# Celestron_Telescope_GPSRX-BT-WiFi-1_10.net
KiCad netlist of a schematic drawn in EAGLE
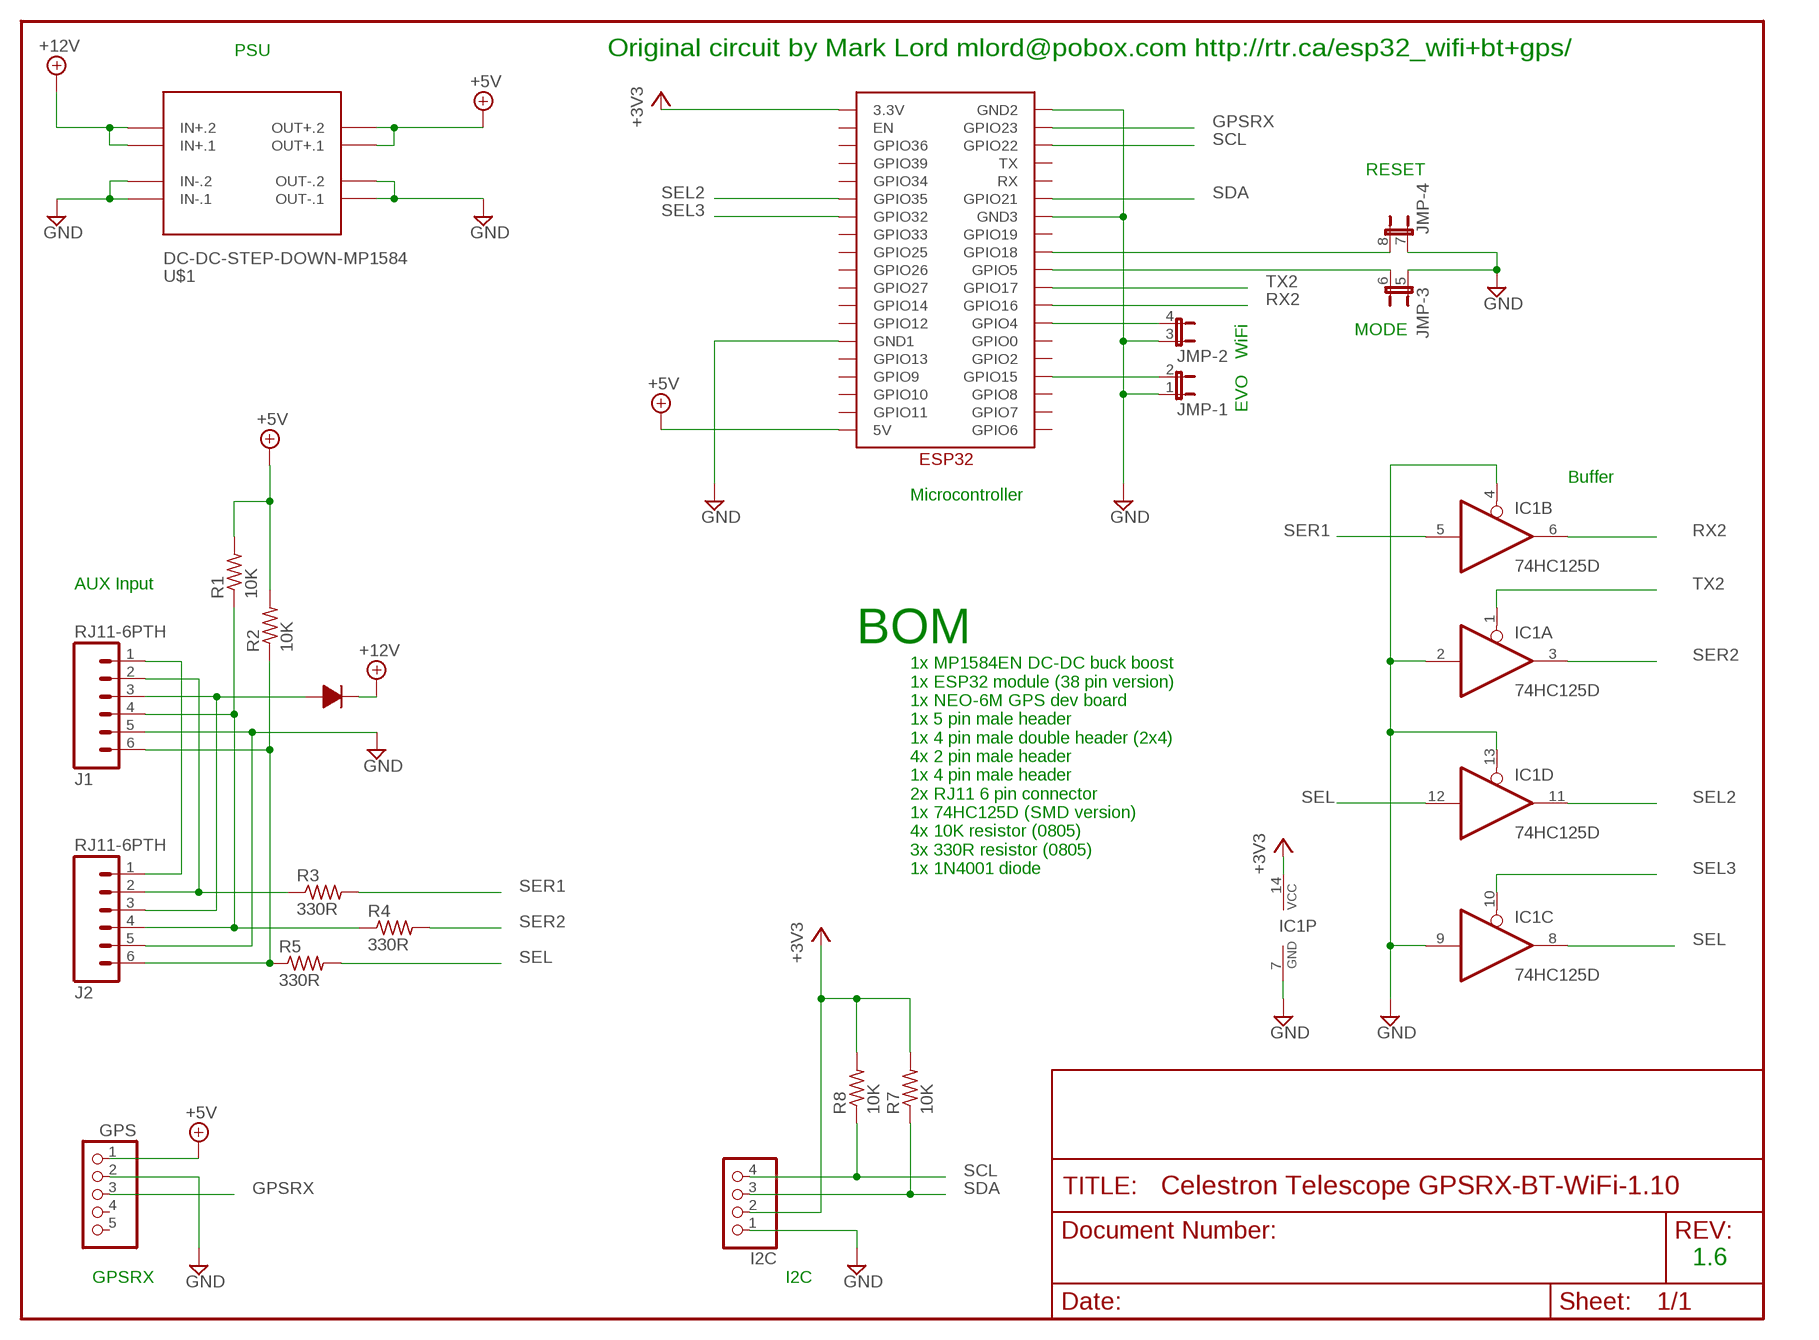
[diagram p0: schematic, sheet 1]

(export (version "E")
  (design (tool "Eeschema 10.0.6"))
  (components
    (comp (ref "GPS")
      (value "PINHD-1X5")
      (footprint "eagle-import:1X05")
      (libsource (lib "eagle-import") (part "PINHD-1X5"))
    )
    (comp (ref "I2C")
      (value "PINHD-1X4")
      (footprint "eagle-import:1X04")
      (libsource (lib "eagle-import") (part "PINHD-1X4"))
    )
    (comp (ref "IC1")
      (value "74HC125D")
      (footprint "eagle-import:SO14")
      (libsource (lib "eagle-import") (part "74125DHC"))
    )
    (comp (ref "J1")
      (value "RJ11-6PTH")
      (footprint "eagle-import:RJ11-6")
      (libsource (lib "eagle-import") (part "RJ11-6PTH"))
    )
    (comp (ref "J2")
      (value "RJ11-6PTH")
      (footprint "eagle-import:RJ11-6")
      (libsource (lib "eagle-import") (part "RJ11-6PTH"))
    )
    (comp (ref "JMP")
      (value "JP4QE")
      (footprint "eagle-import:JP4Q")
      (libsource (lib "eagle-import") (part "JP4QE"))
    )
    (comp (ref "R1")
      (value "10K")
      (footprint "eagle-import:M0805")
      (libsource (lib "eagle-import") (part "R-US_M0805"))
    )
    (comp (ref "R2")
      (value "10K")
      (footprint "eagle-import:M0805")
      (libsource (lib "eagle-import") (part "R-US_M0805"))
    )
    (comp (ref "R3")
      (value "330R")
      (footprint "eagle-import:M0805")
      (libsource (lib "eagle-import") (part "R-US_M0805"))
    )
    (comp (ref "R4")
      (value "330R")
      (footprint "eagle-import:M0805")
      (libsource (lib "eagle-import") (part "R-US_M0805"))
    )
    (comp (ref "R5")
      (value "330R")
      (footprint "eagle-import:M0805")
      (libsource (lib "eagle-import") (part "R-US_M0805"))
    )
    (comp (ref "R7")
      (value "10K")
      (footprint "eagle-import:M0805")
      (libsource (lib "eagle-import") (part "R-US_M0805"))
    )
    (comp (ref "R8")
      (value "10K")
      (footprint "eagle-import:M0805")
      (libsource (lib "eagle-import") (part "R-US_M0805"))
    )
    (comp (ref "U$1")
      (value "DC-DC-STEP-DOWN-MP1584")
      (footprint "eagle-import:DC-DC-STEP-DOWN-MP1584")
      (libsource (lib "eagle-import") (part "DC-DC-STEP-DOWN-MP1584"))
    )
    (comp (ref "U$2")
      (value "1N4001")
      (footprint "eagle-import:DIODE-12.70")
      (libsource (lib "eagle-import") (part "1N4001"))
    )
    (comp (ref "U$3")
      (value "ESP32")
      (footprint "eagle-import:ESP32")
      (libsource (lib "eagle-import") (part "ESP32"))
    )
  )
  (nets
    (net (code "1") (name "+3V3") (class "Default")
      (node (ref "I2C") (pin "2") (pinfunction "2_2") (pintype "passive"))
      (node (ref "IC1") (pin "14") (pinfunction "VCC_14") (pintype "power_in"))
      (node (ref "R7") (pin "2") (pinfunction "2_2") (pintype "passive"))
      (node (ref "R8") (pin "2") (pinfunction "2_2") (pintype "passive"))
      (node (ref "U$3") (pin "3.3V") (pinfunction "3.3V_3.3V") (pintype "bidirectional"))
    )
    (net (code "2") (name "+5V") (class "Default")
      (node (ref "GPS") (pin "1") (pinfunction "1_1") (pintype "passive"))
      (node (ref "R1") (pin "2") (pinfunction "2_2") (pintype "passive"))
      (node (ref "R2") (pin "2") (pinfunction "2_2") (pintype "passive"))
      (node (ref "U$1") (pin "OUT+.1") (pinfunction "OUT+.1_OUT+.1") (pintype "bidirectional"))
      (node (ref "U$1") (pin "OUT+.2") (pinfunction "OUT+.2_OUT+.2") (pintype "bidirectional"))
      (node (ref "U$3") (pin "5V") (pinfunction "5V_5V") (pintype "bidirectional"))
    )
    (net (code "3") (name "+12V") (class "Default")
      (node (ref "U$1") (pin "IN+.1") (pinfunction "IN+.1_IN+.1") (pintype "bidirectional"))
      (node (ref "U$1") (pin "IN+.2") (pinfunction "IN+.2_IN+.2") (pintype "bidirectional"))
      (node (ref "U$2") (pin "P$2") (pinfunction "P$2_P$2") (pintype "passive"))
    )
    (net (code "4") (name "/GPSRX") (class "Default")
      (node (ref "GPS") (pin "3") (pinfunction "3_3") (pintype "passive"))
      (node (ref "U$3") (pin "GPIO23") (pinfunction "GPIO23_GPIO23") (pintype "bidirectional"))
    )
    (net (code "5") (name "/RX2") (class "Default")
      (node (ref "IC1") (pin "6") (pinfunction "O_6") (pintype "tri_state"))
      (node (ref "U$3") (pin "GPIO16") (pinfunction "GPIO16_GPIO16") (pintype "bidirectional"))
    )
    (net (code "6") (name "/SCL") (class "Default")
      (node (ref "I2C") (pin "4") (pinfunction "4_4") (pintype "passive"))
      (node (ref "R8") (pin "1") (pinfunction "1_1") (pintype "passive"))
      (node (ref "U$3") (pin "GPIO22") (pinfunction "GPIO22_GPIO22") (pintype "bidirectional"))
    )
    (net (code "7") (name "/SDA") (class "Default")
      (node (ref "I2C") (pin "3") (pinfunction "3_3") (pintype "passive"))
      (node (ref "R7") (pin "1") (pinfunction "1_1") (pintype "passive"))
      (node (ref "U$3") (pin "GPIO21") (pinfunction "GPIO21_GPIO21") (pintype "bidirectional"))
    )
    (net (code "8") (name "/SEL") (class "Default")
      (node (ref "IC1") (pin "12") (pinfunction "I_12") (pintype "input"))
      (node (ref "IC1") (pin "8") (pinfunction "O_8") (pintype "tri_state"))
      (node (ref "R5") (pin "2") (pinfunction "2_2") (pintype "passive"))
    )
    (net (code "9") (name "/SEL2") (class "Default")
      (node (ref "IC1") (pin "11") (pinfunction "O_11") (pintype "tri_state"))
      (node (ref "U$3") (pin "GPIO35") (pinfunction "GPIO35_GPIO35") (pintype "bidirectional"))
    )
    (net (code "10") (name "/SEL3") (class "Default")
      (node (ref "IC1") (pin "10") (pinfunction "OE_10") (pintype "input"))
      (node (ref "U$3") (pin "GPIO32") (pinfunction "GPIO32_GPIO32") (pintype "bidirectional"))
    )
    (net (code "11") (name "/SER1") (class "Default")
      (node (ref "IC1") (pin "5") (pinfunction "I_5") (pintype "input"))
      (node (ref "R3") (pin "2") (pinfunction "2_2") (pintype "passive"))
    )
    (net (code "12") (name "/SER2") (class "Default")
      (node (ref "IC1") (pin "3") (pinfunction "O_3") (pintype "tri_state"))
      (node (ref "R4") (pin "2") (pinfunction "2_2") (pintype "passive"))
    )
    (net (code "13") (name "/TX2") (class "Default")
      (node (ref "IC1") (pin "1") (pinfunction "OE_1") (pintype "input"))
      (node (ref "U$3") (pin "GPIO17") (pinfunction "GPIO17_GPIO17") (pintype "bidirectional"))
    )
    (net (code "14") (name "GND") (class "Default")
      (node (ref "GPS") (pin "2") (pinfunction "2_2") (pintype "passive"))
      (node (ref "I2C") (pin "1") (pinfunction "1_1") (pintype "passive"))
      (node (ref "IC1") (pin "13") (pinfunction "OE_13") (pintype "input"))
      (node (ref "IC1") (pin "2") (pinfunction "I_2") (pintype "input"))
      (node (ref "IC1") (pin "4") (pinfunction "OE_4") (pintype "input"))
      (node (ref "IC1") (pin "7") (pinfunction "GND_7") (pintype "power_in"))
      (node (ref "IC1") (pin "9") (pinfunction "I_9") (pintype "input"))
      (node (ref "J1") (pin "5") (pinfunction "5_5") (pintype "passive"))
      (node (ref "J2") (pin "5") (pinfunction "5_5") (pintype "passive"))
      (node (ref "JMP") (pin "1") (pinfunction "1_1") (pintype "passive"))
      (node (ref "JMP") (pin "3") (pinfunction "1_3") (pintype "passive"))
      (node (ref "JMP") (pin "5") (pinfunction "1_5") (pintype "passive"))
      (node (ref "JMP") (pin "7") (pinfunction "1_7") (pintype "passive"))
      (node (ref "U$1") (pin "IN-.1") (pinfunction "IN-.1_IN-.1") (pintype "bidirectional"))
      (node (ref "U$1") (pin "IN-.2") (pinfunction "IN-.2_IN-.2") (pintype "bidirectional"))
      (node (ref "U$1") (pin "OUT-.1") (pinfunction "OUT-.1_OUT-.1") (pintype "bidirectional"))
      (node (ref "U$1") (pin "OUT-.2") (pinfunction "OUT-.2_OUT-.2") (pintype "bidirectional"))
      (node (ref "U$3") (pin "GND1") (pinfunction "GND1_GND1") (pintype "bidirectional"))
      (node (ref "U$3") (pin "GND2") (pinfunction "GND2_GND2") (pintype "bidirectional"))
      (node (ref "U$3") (pin "GND3") (pinfunction "GND3_GND3") (pintype "bidirectional"))
    )
    (net (code "15") (name "Net-(J1-Pad1)") (class "Default")
      (node (ref "J1") (pin "1") (pinfunction "1_1") (pintype "passive"))
      (node (ref "J2") (pin "1") (pinfunction "1_1") (pintype "passive"))
    )
    (net (code "16") (name "Net-(J1-Pad2)") (class "Default")
      (node (ref "J1") (pin "2") (pinfunction "2_2") (pintype "passive"))
      (node (ref "J2") (pin "2") (pinfunction "2_2") (pintype "passive"))
      (node (ref "R3") (pin "1") (pinfunction "1_1") (pintype "passive"))
    )
    (net (code "17") (name "Net-(J1-Pad3)") (class "Default")
      (node (ref "J1") (pin "3") (pinfunction "3_3") (pintype "passive"))
      (node (ref "J2") (pin "3") (pinfunction "3_3") (pintype "passive"))
      (node (ref "U$2") (pin "P$1") (pinfunction "P$1_P$1") (pintype "passive"))
    )
    (net (code "18") (name "Net-(J1-Pad4)") (class "Default")
      (node (ref "J1") (pin "4") (pinfunction "4_4") (pintype "passive"))
      (node (ref "J2") (pin "4") (pinfunction "4_4") (pintype "passive"))
      (node (ref "R1") (pin "1") (pinfunction "1_1") (pintype "passive"))
      (node (ref "R4") (pin "1") (pinfunction "1_1") (pintype "passive"))
    )
    (net (code "19") (name "Net-(J1-Pad6)") (class "Default")
      (node (ref "J1") (pin "6") (pinfunction "6_6") (pintype "passive"))
      (node (ref "J2") (pin "6") (pinfunction "6_6") (pintype "passive"))
      (node (ref "R2") (pin "1") (pinfunction "1_1") (pintype "passive"))
      (node (ref "R5") (pin "1") (pinfunction "1_1") (pintype "passive"))
    )
    (net (code "20") (name "Net-(JMP-Pad2)") (class "Default")
      (node (ref "JMP") (pin "2") (pinfunction "2_2") (pintype "passive"))
      (node (ref "U$3") (pin "GPIO15") (pinfunction "GPIO15_GPIO15") (pintype "bidirectional"))
    )
    (net (code "21") (name "Net-(JMPB-2)") (class "Default")
      (node (ref "JMP") (pin "4") (pinfunction "2_4") (pintype "passive"))
      (node (ref "U$3") (pin "GPIO4") (pinfunction "GPIO4_GPIO4") (pintype "bidirectional"))
    )
    (net (code "22") (name "Net-(JMPC-2)") (class "Default")
      (node (ref "JMP") (pin "6") (pinfunction "2_6") (pintype "passive"))
      (node (ref "U$3") (pin "GPIO5") (pinfunction "GPIO5_GPIO5") (pintype "bidirectional"))
    )
    (net (code "23") (name "Net-(JMPD-2)") (class "Default")
      (node (ref "JMP") (pin "8") (pinfunction "2_8") (pintype "passive"))
      (node (ref "U$3") (pin "GPIO18") (pinfunction "GPIO18_GPIO18") (pintype "bidirectional"))
    )
    (net (code "24") (name "unconnected-(GPS-Pad4)") (class "Default")
      (node (ref "GPS") (pin "4") (pinfunction "4_4") (pintype "passive"))
    )
    (net (code "25") (name "unconnected-(GPS-Pad5)") (class "Default")
      (node (ref "GPS") (pin "5") (pinfunction "5_5") (pintype "passive"))
    )
    (net (code "26") (name "unconnected-(U$3-PadEN)") (class "Default")
      (node (ref "U$3") (pin "EN") (pinfunction "EN_EN") (pintype "bidirectional"))
    )
    (net (code "27") (name "unconnected-(U$3-PadGPIO0)") (class "Default")
      (node (ref "U$3") (pin "GPIO0") (pinfunction "GPIO0_GPIO0") (pintype "bidirectional"))
    )
    (net (code "28") (name "unconnected-(U$3-PadGPIO2)") (class "Default")
      (node (ref "U$3") (pin "GPIO2") (pinfunction "GPIO2_GPIO2") (pintype "bidirectional"))
    )
    (net (code "29") (name "unconnected-(U$3-PadGPIO6)") (class "Default")
      (node (ref "U$3") (pin "GPIO6") (pinfunction "GPIO6_GPIO6") (pintype "bidirectional"))
    )
    (net (code "30") (name "unconnected-(U$3-PadGPIO7)") (class "Default")
      (node (ref "U$3") (pin "GPIO7") (pinfunction "GPIO7_GPIO7") (pintype "bidirectional"))
    )
    (net (code "31") (name "unconnected-(U$3-PadGPIO8)") (class "Default")
      (node (ref "U$3") (pin "GPIO8") (pinfunction "GPIO8_GPIO8") (pintype "bidirectional"))
    )
    (net (code "32") (name "unconnected-(U$3-PadGPIO9)") (class "Default")
      (node (ref "U$3") (pin "GPIO9") (pinfunction "GPIO9_GPIO9") (pintype "bidirectional"))
    )
    (net (code "33") (name "unconnected-(U$3-PadGPIO10)") (class "Default")
      (node (ref "U$3") (pin "GPIO10") (pinfunction "GPIO10_GPIO10") (pintype "bidirectional"))
    )
    (net (code "34") (name "unconnected-(U$3-PadGPIO11)") (class "Default")
      (node (ref "U$3") (pin "GPIO11") (pinfunction "GPIO11_GPIO11") (pintype "bidirectional"))
    )
    (net (code "35") (name "unconnected-(U$3-PadGPIO12)") (class "Default")
      (node (ref "U$3") (pin "GPIO12") (pinfunction "GPIO12_GPIO12") (pintype "bidirectional"))
    )
    (net (code "36") (name "unconnected-(U$3-PadGPIO13)") (class "Default")
      (node (ref "U$3") (pin "GPIO13") (pinfunction "GPIO13_GPIO13") (pintype "bidirectional"))
    )
    (net (code "37") (name "unconnected-(U$3-PadGPIO14)") (class "Default")
      (node (ref "U$3") (pin "GPIO14") (pinfunction "GPIO14_GPIO14") (pintype "bidirectional"))
    )
    (net (code "38") (name "unconnected-(U$3-PadGPIO19)") (class "Default")
      (node (ref "U$3") (pin "GPIO19") (pinfunction "GPIO19_GPIO19") (pintype "bidirectional"))
    )
    (net (code "39") (name "unconnected-(U$3-PadGPIO25)") (class "Default")
      (node (ref "U$3") (pin "GPIO25") (pinfunction "GPIO25_GPIO25") (pintype "bidirectional"))
    )
    (net (code "40") (name "unconnected-(U$3-PadGPIO26)") (class "Default")
      (node (ref "U$3") (pin "GPIO26") (pinfunction "GPIO26_GPIO26") (pintype "bidirectional"))
    )
    (net (code "41") (name "unconnected-(U$3-PadGPIO27)") (class "Default")
      (node (ref "U$3") (pin "GPIO27") (pinfunction "GPIO27_GPIO27") (pintype "bidirectional"))
    )
    (net (code "42") (name "unconnected-(U$3-PadGPIO33)") (class "Default")
      (node (ref "U$3") (pin "GPIO33") (pinfunction "GPIO33_GPIO33") (pintype "bidirectional"))
    )
    (net (code "43") (name "unconnected-(U$3-PadGPIO34)") (class "Default")
      (node (ref "U$3") (pin "GPIO34") (pinfunction "GPIO34_GPIO34") (pintype "bidirectional"))
    )
    (net (code "44") (name "unconnected-(U$3-PadGPIO36)") (class "Default")
      (node (ref "U$3") (pin "GPIO36") (pinfunction "GPIO36_GPIO36") (pintype "bidirectional"))
    )
    (net (code "45") (name "unconnected-(U$3-PadGPIO39)") (class "Default")
      (node (ref "U$3") (pin "GPIO39") (pinfunction "GPIO39_GPIO39") (pintype "bidirectional"))
    )
    (net (code "46") (name "unconnected-(U$3-PadRX)") (class "Default")
      (node (ref "U$3") (pin "RX") (pinfunction "RX_RX") (pintype "bidirectional"))
    )
    (net (code "47") (name "unconnected-(U$3-PadTX)") (class "Default")
      (node (ref "U$3") (pin "TX") (pinfunction "TX_TX") (pintype "bidirectional"))
    )
  )
)
